# tank_interface.net
KiCad netlist of a schematic drawn in EAGLE
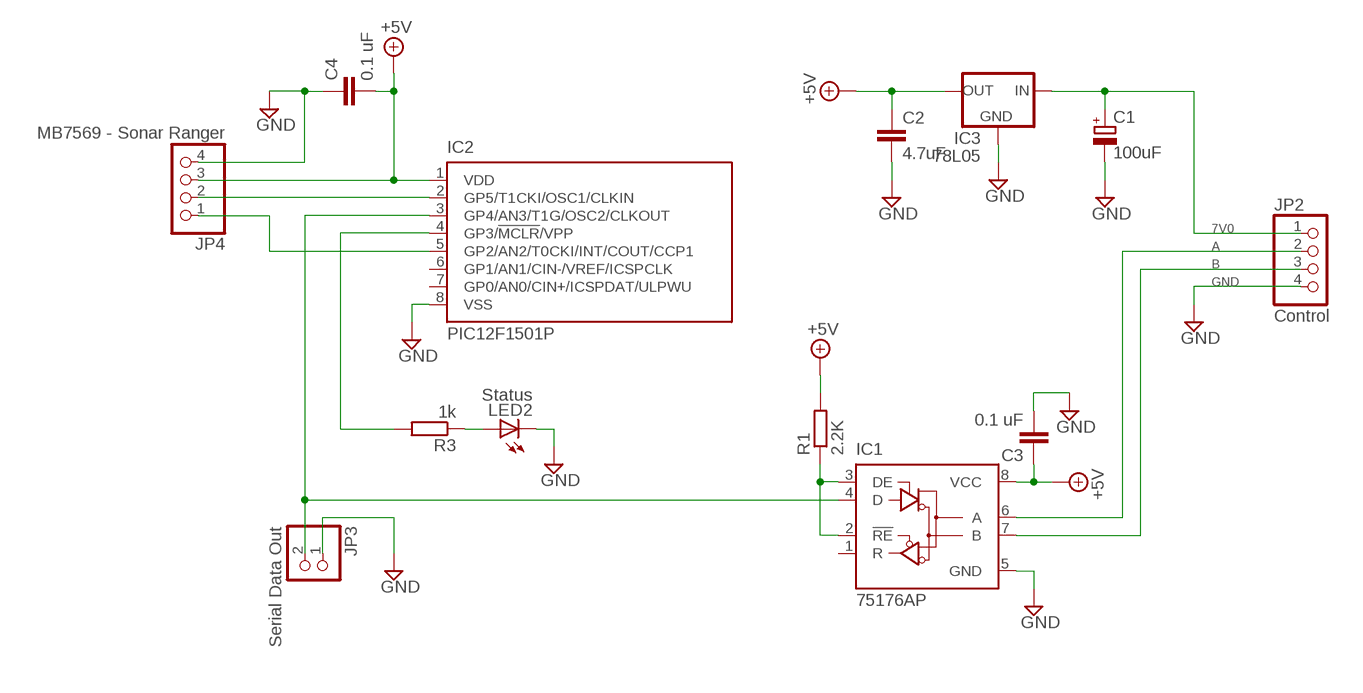
[diagram p0: schematic, sheet 1]

(export (version "E")
  (design (tool "Eeschema 10.0.6"))
  (components
    (comp (ref "C1")
      (value "100uF")
      (footprint "eagle-import:E2,5-7")
      (libsource (lib "eagle-import") (part "CPOL-EUE2.5-7"))
    )
    (comp (ref "C2")
      (value "4.7uF")
      (footprint "eagle-import:C0402")
      (libsource (lib "eagle-import") (part "C-EUC0402"))
    )
    (comp (ref "C3")
      (value "0.1 uF")
      (footprint "eagle-import:C0402")
      (libsource (lib "eagle-import") (part "C-EUC0402"))
    )
    (comp (ref "C4")
      (value "0.1 uF")
      (footprint "eagle-import:C0402")
      (libsource (lib "eagle-import") (part "C-EUC0402"))
    )
    (comp (ref "IC1")
      (value "75176AP")
      (footprint "eagle-import:DIL08")
      (libsource (lib "eagle-import") (part "75176AP"))
    )
    (comp (ref "IC2")
      (value "PIC12F1501P")
      (footprint "eagle-import:DIL8")
      (fields (field (name "MF") "MICROCHIP") (field (name "MPN") "PIC12F683-I/P"))
      (libsource (lib "eagle-import") (part "PIC12F683P"))
    )
    (comp (ref "IC3")
      (value "78L05")
      (footprint "eagle-import:78XXS")
      (libsource (lib "eagle-import") (part "78XXS"))
    )
    (comp (ref "JP2")
      (value "Control")
      (footprint "eagle-import:1X04")
      (libsource (lib "eagle-import") (part "PINHD-1X4"))
    )
    (comp (ref "JP3")
      (value "Serial Data Out")
      (footprint "eagle-import:1X02")
      (libsource (lib "eagle-import") (part "PINHD-1X2"))
    )
    (comp (ref "JP4")
      (value "MB7569 - Sonar Ranger")
      (footprint "eagle-import:1X04")
      (libsource (lib "eagle-import") (part "PINHD-1X4"))
    )
    (comp (ref "LED2")
      (value "Status")
      (footprint "eagle-import:LED3MM")
      (libsource (lib "eagle-import") (part "LED3MM"))
    )
    (comp (ref "R1")
      (value "2.2K")
      (footprint "eagle-import:R0603")
      (libsource (lib "eagle-import") (part "R-EU_R0603"))
    )
    (comp (ref "R3")
      (value "1k")
      (footprint "eagle-import:R0603")
      (libsource (lib "eagle-import") (part "R-EU_R0603"))
    )
  )
  (nets
    (net (code "1") (name "+5V") (class "Default")
      (node (ref "C2") (pin "1") (pinfunction "1_1") (pintype "passive"))
      (node (ref "C3") (pin "1") (pinfunction "1_1") (pintype "passive"))
      (node (ref "C4") (pin "2") (pinfunction "2_2") (pintype "passive"))
      (node (ref "IC1") (pin "8") (pinfunction "VCC_8") (pintype "power_in"))
      (node (ref "IC2") (pin "1") (pinfunction "VDD_1") (pintype "power_in"))
      (node (ref "IC3") (pin "OUT") (pinfunction "OUT_OUT") (pintype "passive"))
      (node (ref "JP4") (pin "3") (pinfunction "3_3") (pintype "passive"))
      (node (ref "R1") (pin "2") (pinfunction "2_2") (pintype "passive"))
    )
    (net (code "2") (name "/7V0") (class "Default")
      (node (ref "C1") (pin "+") (pinfunction "+_+") (pintype "passive"))
      (node (ref "IC3") (pin "IN") (pinfunction "IN_IN") (pintype "input"))
      (node (ref "JP2") (pin "1") (pinfunction "1_1") (pintype "passive"))
    )
    (net (code "3") (name "/A") (class "Default")
      (node (ref "IC1") (pin "6") (pinfunction "A_6") (pintype "output"))
      (node (ref "JP2") (pin "2") (pinfunction "2_2") (pintype "passive"))
    )
    (net (code "4") (name "/B") (class "Default")
      (node (ref "IC1") (pin "7") (pinfunction "B_7") (pintype "output"))
      (node (ref "JP2") (pin "3") (pinfunction "3_3") (pintype "passive"))
    )
    (net (code "5") (name "GND") (class "Default")
      (node (ref "C1") (pin "-") (pinfunction "-_-") (pintype "passive"))
      (node (ref "C2") (pin "2") (pinfunction "2_2") (pintype "passive"))
      (node (ref "C3") (pin "2") (pinfunction "2_2") (pintype "passive"))
      (node (ref "C4") (pin "1") (pinfunction "1_1") (pintype "passive"))
      (node (ref "IC1") (pin "5") (pinfunction "GND_5") (pintype "power_in"))
      (node (ref "IC2") (pin "8") (pinfunction "VSS_8") (pintype "power_in"))
      (node (ref "IC3") (pin "GND") (pinfunction "GND_GND") (pintype "input"))
      (node (ref "JP2") (pin "4") (pinfunction "4_4") (pintype "passive"))
      (node (ref "JP3") (pin "1") (pinfunction "1_1") (pintype "passive"))
      (node (ref "JP4") (pin "4") (pinfunction "4_4") (pintype "passive"))
      (node (ref "LED2") (pin "K") (pinfunction "C_K") (pintype "passive"))
    )
    (net (code "6") (name "Net-(IC1-D)") (class "Default")
      (node (ref "IC1") (pin "4") (pinfunction "D_4") (pintype "input"))
      (node (ref "IC2") (pin "3") (pinfunction "GP4/AN3/T1G/OSC2/CLKOUT_3") (pintype "bidirectional"))
      (node (ref "JP3") (pin "2") (pinfunction "2_2") (pintype "passive"))
    )
    (net (code "7") (name "Net-(IC1-DE)") (class "Default")
      (node (ref "IC1") (pin "2") (pinfunction "~{RE}_2") (pintype "input"))
      (node (ref "IC1") (pin "3") (pinfunction "DE_3") (pintype "input"))
      (node (ref "R1") (pin "1") (pinfunction "1_1") (pintype "passive"))
    )
    (net (code "8") (name "Net-(IC2-GP2{slash}AN2{slash}T0CKI{slash}INT{slash}COUT{slash}CCP1)") (class "Default")
      (node (ref "IC2") (pin "5") (pinfunction "GP2/AN2/T0CKI/INT/COUT/CCP1_5") (pintype "bidirectional"))
      (node (ref "JP4") (pin "1") (pinfunction "1_1") (pintype "passive"))
    )
    (net (code "9") (name "Net-(IC2-GP3{slash}~{MCLR}{slash}VPP)") (class "Default")
      (node (ref "IC2") (pin "4") (pinfunction "GP3/~{MCLR}/VPP_4") (pintype "bidirectional"))
      (node (ref "R3") (pin "2") (pinfunction "2_2") (pintype "passive"))
    )
    (net (code "10") (name "Net-(IC2-GP5{slash}T1CKI{slash}OSC1{slash}CLKIN)") (class "Default")
      (node (ref "IC2") (pin "2") (pinfunction "GP5/T1CKI/OSC1/CLKIN_2") (pintype "bidirectional"))
      (node (ref "JP4") (pin "2") (pinfunction "2_2") (pintype "passive"))
    )
    (net (code "11") (name "Net-(LED2-PadA)") (class "Default")
      (node (ref "LED2") (pin "A") (pinfunction "A_A") (pintype "passive"))
      (node (ref "R3") (pin "1") (pinfunction "1_1") (pintype "passive"))
    )
    (net (code "12") (name "unconnected-(IC1-R-Pad1)") (class "Default")
      (node (ref "IC1") (pin "1") (pinfunction "R_1") (pintype "output"))
    )
    (net (code "13") (name "unconnected-(IC2-GP0{slash}AN0{slash}CIN+{slash}ICSPDAT{slash}ULPWU-Pad7)") (class "Default")
      (node (ref "IC2") (pin "7") (pinfunction "GP0/AN0/CIN+/ICSPDAT/ULPWU_7") (pintype "bidirectional"))
    )
    (net (code "14") (name "unconnected-(IC2-GP1{slash}AN1{slash}CIN-{slash}VREF{slash}ICSPCLK-Pad6)") (class "Default")
      (node (ref "IC2") (pin "6") (pinfunction "GP1/AN1/CIN-/VREF/ICSPCLK_6") (pintype "bidirectional"))
    )
  )
)
